# ZYNQ_BANK.net
KiCad netlist of a schematic drawn in Altium Designer
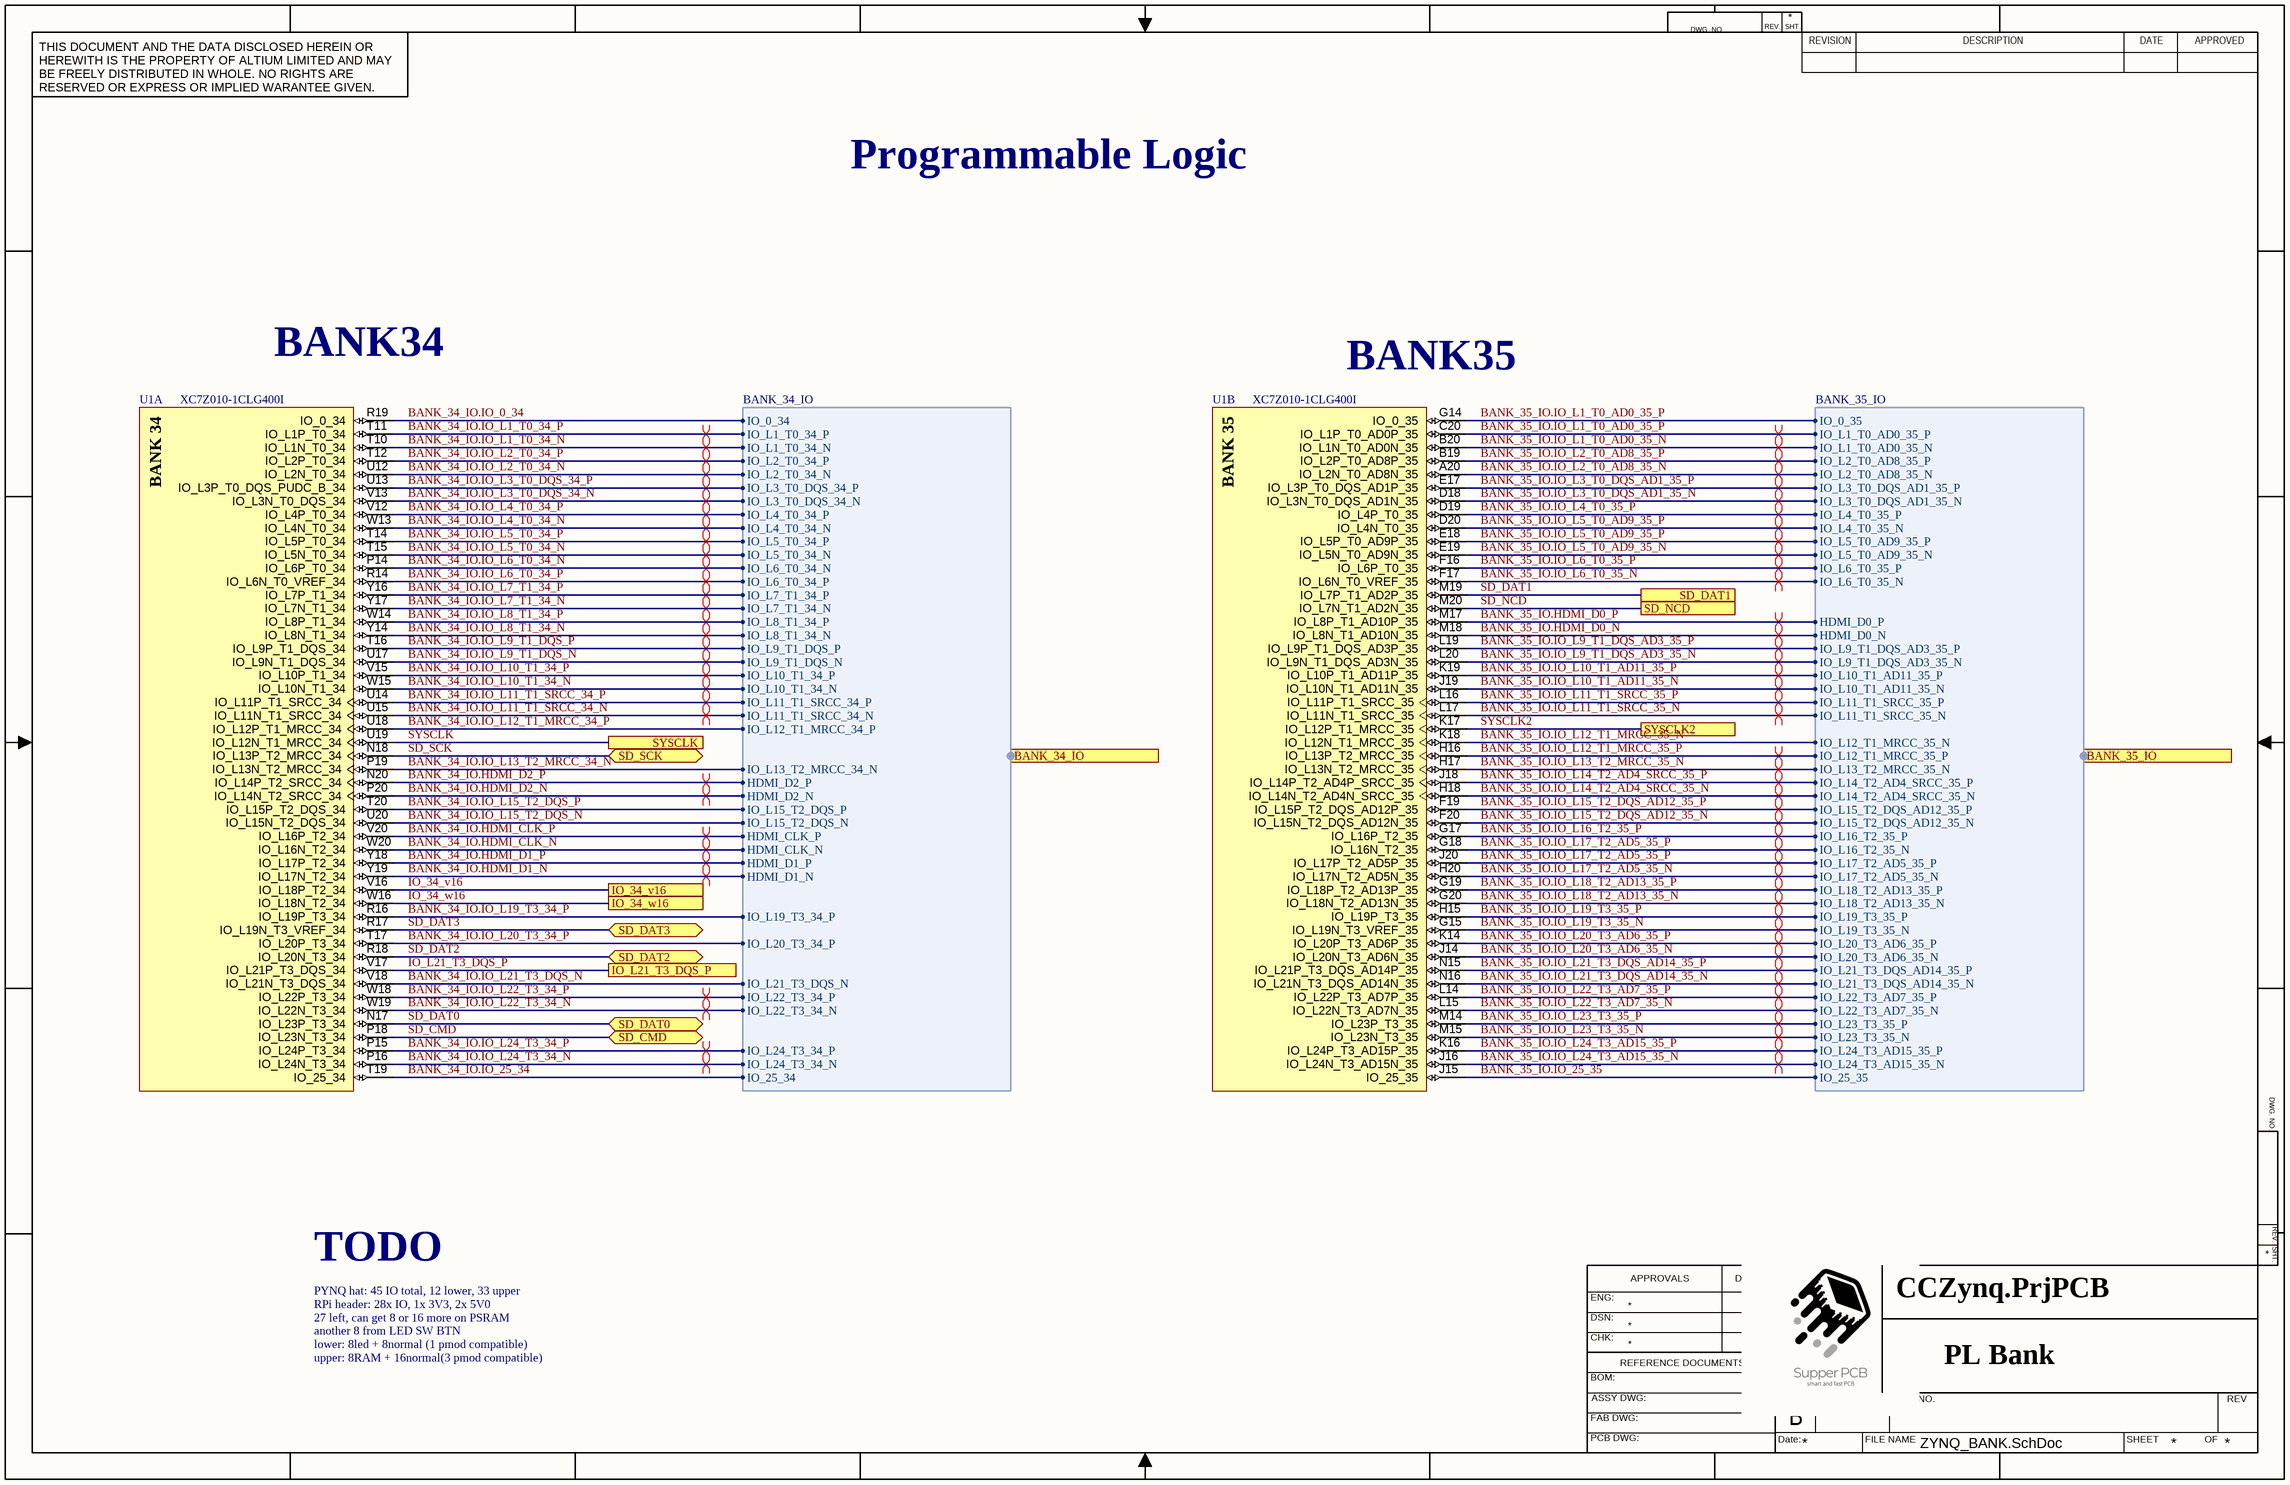
[diagram p0: ZYNQ_BANK.SchDoc]

(export (version "E")
  (design (tool "Eeschema 10.0.6"))
  (components
    (comp (ref "U1")
      (value "XC7Z010-1CLG400I")
      (footprint "CLG400")
      (fields (field (name "GENERIC PART NUMBER") "XC7Z010") (field (name "MANUFACTURER") "Xilinx"))
      (libsource (lib "CCZynq") (part "XC7Z010-1CLG400I"))
    )
  )
  (nets
    (net (code "3") (name "/BANK_34_IO.HDMI_CLK_N") (class "Default")
      (node (ref "U1") (pin "W20") (pinfunction "IO_L16N_T2_34_W20") (pintype "bidirectional"))
    )
    (net (code "4") (name "/BANK_34_IO.HDMI_CLK_P") (class "Default")
      (node (ref "U1") (pin "V20") (pinfunction "IO_L16P_T2_34_V20") (pintype "bidirectional"))
    )
    (net (code "5") (name "/BANK_34_IO.HDMI_D1_N") (class "Default")
      (node (ref "U1") (pin "Y19") (pinfunction "IO_L17N_T2_34_Y19") (pintype "bidirectional"))
    )
    (net (code "6") (name "/BANK_34_IO.HDMI_D1_P") (class "Default")
      (node (ref "U1") (pin "Y18") (pinfunction "IO_L17P_T2_34_Y18") (pintype "bidirectional"))
    )
    (net (code "7") (name "/BANK_34_IO.HDMI_D2_N") (class "Default")
      (node (ref "U1") (pin "P20") (pinfunction "IO_L14N_T2_SRCC_34_P20") (pintype "bidirectional"))
    )
    (net (code "8") (name "/BANK_34_IO.HDMI_D2_P") (class "Default")
      (node (ref "U1") (pin "N20") (pinfunction "IO_L14P_T2_SRCC_34_N20") (pintype "bidirectional"))
    )
    (net (code "9") (name "/BANK_34_IO.IO_0_34") (class "Default")
      (node (ref "U1") (pin "R19") (pinfunction "IO_0_34_R19") (pintype "bidirectional"))
    )
    (net (code "10") (name "/BANK_34_IO.IO_25_34") (class "Default")
      (node (ref "U1") (pin "T19") (pinfunction "IO_25_34_T19") (pintype "bidirectional"))
    )
    (net (code "11") (name "/BANK_34_IO.IO_L1_T0_34_N") (class "Default")
      (node (ref "U1") (pin "T10") (pinfunction "IO_L1N_T0_34_T10") (pintype "bidirectional"))
    )
    (net (code "12") (name "/BANK_34_IO.IO_L1_T0_34_P") (class "Default")
      (node (ref "U1") (pin "T11") (pinfunction "IO_L1P_T0_34_T11") (pintype "bidirectional"))
    )
    (net (code "13") (name "/BANK_34_IO.IO_L2_T0_34_N") (class "Default")
      (node (ref "U1") (pin "U12") (pinfunction "IO_L2N_T0_34_U12") (pintype "bidirectional"))
    )
    (net (code "14") (name "/BANK_34_IO.IO_L2_T0_34_P") (class "Default")
      (node (ref "U1") (pin "T12") (pinfunction "IO_L2P_T0_34_T12") (pintype "bidirectional"))
    )
    (net (code "15") (name "/BANK_34_IO.IO_L3_T0_DQS_34_N") (class "Default")
      (node (ref "U1") (pin "V13") (pinfunction "IO_L3N_T0_DQS_34_V13") (pintype "bidirectional"))
    )
    (net (code "16") (name "/BANK_34_IO.IO_L3_T0_DQS_34_P") (class "Default")
      (node (ref "U1") (pin "U13") (pinfunction "IO_L3P_T0_DQS_PUDC_B_34_U13") (pintype "bidirectional"))
    )
    (net (code "17") (name "/BANK_34_IO.IO_L4_T0_34_N") (class "Default")
      (node (ref "U1") (pin "W13") (pinfunction "IO_L4N_T0_34_W13") (pintype "bidirectional"))
    )
    (net (code "18") (name "/BANK_34_IO.IO_L4_T0_34_P") (class "Default")
      (node (ref "U1") (pin "V12") (pinfunction "IO_L4P_T0_34_V12") (pintype "bidirectional"))
    )
    (net (code "19") (name "/BANK_34_IO.IO_L5_T0_34_N") (class "Default")
      (node (ref "U1") (pin "T15") (pinfunction "IO_L5N_T0_34_T15") (pintype "bidirectional"))
    )
    (net (code "20") (name "/BANK_34_IO.IO_L5_T0_34_P") (class "Default")
      (node (ref "U1") (pin "T14") (pinfunction "IO_L5P_T0_34_T14") (pintype "bidirectional"))
    )
    (net (code "21") (name "/BANK_34_IO.IO_L6_T0_34_N") (class "Default")
      (node (ref "U1") (pin "P14") (pinfunction "IO_L6P_T0_34_P14") (pintype "bidirectional"))
    )
    (net (code "22") (name "/BANK_34_IO.IO_L6_T0_34_P") (class "Default")
      (node (ref "U1") (pin "R14") (pinfunction "IO_L6N_T0_VREF_34_R14") (pintype "bidirectional"))
    )
    (net (code "23") (name "/BANK_34_IO.IO_L7_T1_34_N") (class "Default")
      (node (ref "U1") (pin "Y17") (pinfunction "IO_L7N_T1_34_Y17") (pintype "bidirectional"))
    )
    (net (code "24") (name "/BANK_34_IO.IO_L7_T1_34_P") (class "Default")
      (node (ref "U1") (pin "Y16") (pinfunction "IO_L7P_T1_34_Y16") (pintype "bidirectional"))
    )
    (net (code "25") (name "/BANK_34_IO.IO_L8_T1_34_N") (class "Default")
      (node (ref "U1") (pin "Y14") (pinfunction "IO_L8N_T1_34_Y14") (pintype "bidirectional"))
    )
    (net (code "26") (name "/BANK_34_IO.IO_L8_T1_34_P") (class "Default")
      (node (ref "U1") (pin "W14") (pinfunction "IO_L8P_T1_34_W14") (pintype "bidirectional"))
    )
    (net (code "27") (name "/BANK_34_IO.IO_L9_T1_DQS_N") (class "Default")
      (node (ref "U1") (pin "U17") (pinfunction "IO_L9N_T1_DQS_34_U17") (pintype "bidirectional"))
    )
    (net (code "28") (name "/BANK_34_IO.IO_L9_T1_DQS_P") (class "Default")
      (node (ref "U1") (pin "T16") (pinfunction "IO_L9P_T1_DQS_34_T16") (pintype "bidirectional"))
    )
    (net (code "29") (name "/BANK_34_IO.IO_L10_T1_34_N") (class "Default")
      (node (ref "U1") (pin "W15") (pinfunction "IO_L10N_T1_34_W15") (pintype "bidirectional"))
    )
    (net (code "30") (name "/BANK_34_IO.IO_L10_T1_34_P") (class "Default")
      (node (ref "U1") (pin "V15") (pinfunction "IO_L10P_T1_34_V15") (pintype "bidirectional"))
    )
    (net (code "31") (name "/BANK_34_IO.IO_L11_T1_SRCC_34_N") (class "Default")
      (node (ref "U1") (pin "U15") (pinfunction "IO_L11N_T1_SRCC_34_U15") (pintype "bidirectional"))
    )
    (net (code "32") (name "/BANK_34_IO.IO_L11_T1_SRCC_34_P") (class "Default")
      (node (ref "U1") (pin "U14") (pinfunction "IO_L11P_T1_SRCC_34_U14") (pintype "bidirectional"))
    )
    (net (code "33") (name "/BANK_34_IO.IO_L12_T1_MRCC_34_P") (class "Default")
      (node (ref "U1") (pin "U18") (pinfunction "IO_L12P_T1_MRCC_34_U18") (pintype "bidirectional"))
    )
    (net (code "34") (name "/BANK_34_IO.IO_L13_T2_MRCC_34_N") (class "Default")
      (node (ref "U1") (pin "P19") (pinfunction "IO_L13N_T2_MRCC_34_P19") (pintype "bidirectional"))
    )
    (net (code "35") (name "/BANK_34_IO.IO_L15_T2_DQS_N") (class "Default")
      (node (ref "U1") (pin "U20") (pinfunction "IO_L15N_T2_DQS_34_U20") (pintype "bidirectional"))
    )
    (net (code "36") (name "/BANK_34_IO.IO_L15_T2_DQS_P") (class "Default")
      (node (ref "U1") (pin "T20") (pinfunction "IO_L15P_T2_DQS_34_T20") (pintype "bidirectional"))
    )
    (net (code "37") (name "/BANK_34_IO.IO_L19_T3_34_P") (class "Default")
      (node (ref "U1") (pin "R16") (pinfunction "IO_L19P_T3_34_R16") (pintype "bidirectional"))
    )
    (net (code "38") (name "/BANK_34_IO.IO_L20_T3_34_P") (class "Default")
      (node (ref "U1") (pin "T17") (pinfunction "IO_L20P_T3_34_T17") (pintype "bidirectional"))
    )
    (net (code "39") (name "/BANK_34_IO.IO_L21_T3_DQS_N") (class "Default")
      (node (ref "U1") (pin "V18") (pinfunction "IO_L21N_T3_DQS_34_V18") (pintype "bidirectional"))
    )
    (net (code "40") (name "/BANK_34_IO.IO_L22_T3_34_N") (class "Default")
      (node (ref "U1") (pin "W19") (pinfunction "IO_L22N_T3_34_W19") (pintype "bidirectional"))
    )
    (net (code "41") (name "/BANK_34_IO.IO_L22_T3_34_P") (class "Default")
      (node (ref "U1") (pin "W18") (pinfunction "IO_L22P_T3_34_W18") (pintype "bidirectional"))
    )
    (net (code "42") (name "/BANK_34_IO.IO_L24_T3_34_N") (class "Default")
      (node (ref "U1") (pin "P16") (pinfunction "IO_L24N_T3_34_P16") (pintype "bidirectional"))
    )
    (net (code "43") (name "/BANK_34_IO.IO_L24_T3_34_P") (class "Default")
      (node (ref "U1") (pin "P15") (pinfunction "IO_L24P_T3_34_P15") (pintype "bidirectional"))
    )
    (net (code "44") (name "/BANK_35_IO.HDMI_D0_N") (class "Default")
      (node (ref "U1") (pin "M18") (pinfunction "IO_L8N_T1_AD10N_35_M18") (pintype "bidirectional"))
    )
    (net (code "45") (name "/BANK_35_IO.HDMI_D0_P") (class "Default")
      (node (ref "U1") (pin "M17") (pinfunction "IO_L8P_T1_AD10P_35_M17") (pintype "bidirectional"))
    )
    (net (code "46") (name "/BANK_35_IO.IO_25_35") (class "Default")
      (node (ref "U1") (pin "J15") (pinfunction "IO_25_35_J15") (pintype "bidirectional"))
    )
    (net (code "47") (name "/BANK_35_IO.IO_L1_T0_AD0_35_N") (class "Default")
      (node (ref "U1") (pin "B20") (pinfunction "IO_L1N_T0_AD0N_35_B20") (pintype "bidirectional"))
    )
    (net (code "48") (name "/BANK_35_IO.IO_L1_T0_AD0_35_P") (class "Default")
      (node (ref "U1") (pin "C20") (pinfunction "IO_L1P_T0_AD0P_35_C20") (pintype "bidirectional"))
      (node (ref "U1") (pin "G14") (pinfunction "IO_0_35_G14") (pintype "bidirectional"))
    )
    (net (code "49") (name "/BANK_35_IO.IO_L2_T0_AD8_35_N") (class "Default")
      (node (ref "U1") (pin "A20") (pinfunction "IO_L2N_T0_AD8N_35_A20") (pintype "bidirectional"))
    )
    (net (code "50") (name "/BANK_35_IO.IO_L2_T0_AD8_35_P") (class "Default")
      (node (ref "U1") (pin "B19") (pinfunction "IO_L2P_T0_AD8P_35_B19") (pintype "bidirectional"))
    )
    (net (code "51") (name "/BANK_35_IO.IO_L3_T0_DQS_AD1_35_N") (class "Default")
      (node (ref "U1") (pin "D18") (pinfunction "IO_L3N_T0_DQS_AD1N_35_D18") (pintype "bidirectional"))
    )
    (net (code "52") (name "/BANK_35_IO.IO_L3_T0_DQS_AD1_35_P") (class "Default")
      (node (ref "U1") (pin "E17") (pinfunction "IO_L3P_T0_DQS_AD1P_35_E17") (pintype "bidirectional"))
    )
    (net (code "53") (name "/BANK_35_IO.IO_L4_T0_35_P") (class "Default")
      (node (ref "U1") (pin "D19") (pinfunction "IO_L4P_T0_35_D19") (pintype "bidirectional"))
    )
    (net (code "54") (name "/BANK_35_IO.IO_L5_T0_AD9_35_N") (class "Default")
      (node (ref "U1") (pin "E19") (pinfunction "IO_L5N_T0_AD9N_35_E19") (pintype "bidirectional"))
    )
    (net (code "55") (name "/BANK_35_IO.IO_L5_T0_AD9_35_P") (class "Default")
      (node (ref "U1") (pin "D20") (pinfunction "IO_L4N_T0_35_D20") (pintype "bidirectional"))
      (node (ref "U1") (pin "E18") (pinfunction "IO_L5P_T0_AD9P_35_E18") (pintype "bidirectional"))
    )
    (net (code "56") (name "/BANK_35_IO.IO_L6_T0_35_N") (class "Default")
      (node (ref "U1") (pin "F17") (pinfunction "IO_L6N_T0_VREF_35_F17") (pintype "bidirectional"))
    )
    (net (code "57") (name "/BANK_35_IO.IO_L6_T0_35_P") (class "Default")
      (node (ref "U1") (pin "F16") (pinfunction "IO_L6P_T0_35_F16") (pintype "bidirectional"))
    )
    (net (code "58") (name "/BANK_35_IO.IO_L9_T1_DQS_AD3_35_N") (class "Default")
      (node (ref "U1") (pin "L20") (pinfunction "IO_L9N_T1_DQS_AD3N_35_L20") (pintype "bidirectional"))
    )
    (net (code "59") (name "/BANK_35_IO.IO_L9_T1_DQS_AD3_35_P") (class "Default")
      (node (ref "U1") (pin "L19") (pinfunction "IO_L9P_T1_DQS_AD3P_35_L19") (pintype "bidirectional"))
    )
    (net (code "60") (name "/BANK_35_IO.IO_L10_T1_AD11_35_N") (class "Default")
      (node (ref "U1") (pin "J19") (pinfunction "IO_L10N_T1_AD11N_35_J19") (pintype "bidirectional"))
    )
    (net (code "61") (name "/BANK_35_IO.IO_L10_T1_AD11_35_P") (class "Default")
      (node (ref "U1") (pin "K19") (pinfunction "IO_L10P_T1_AD11P_35_K19") (pintype "bidirectional"))
    )
    (net (code "62") (name "/BANK_35_IO.IO_L11_T1_SRCC_35_N") (class "Default")
      (node (ref "U1") (pin "L17") (pinfunction "IO_L11N_T1_SRCC_35_L17") (pintype "bidirectional"))
    )
    (net (code "63") (name "/BANK_35_IO.IO_L11_T1_SRCC_35_P") (class "Default")
      (node (ref "U1") (pin "L16") (pinfunction "IO_L11P_T1_SRCC_35_L16") (pintype "bidirectional"))
    )
    (net (code "64") (name "/BANK_35_IO.IO_L12_T1_MRCC_35_N") (class "Default")
      (node (ref "U1") (pin "K18") (pinfunction "IO_L12N_T1_MRCC_35_K18") (pintype "bidirectional"))
    )
    (net (code "65") (name "/BANK_35_IO.IO_L12_T1_MRCC_35_P") (class "Default")
      (node (ref "U1") (pin "H16") (pinfunction "IO_L13P_T2_MRCC_35_H16") (pintype "bidirectional"))
    )
    (net (code "66") (name "/BANK_35_IO.IO_L13_T2_MRCC_35_N") (class "Default")
      (node (ref "U1") (pin "H17") (pinfunction "IO_L13N_T2_MRCC_35_H17") (pintype "bidirectional"))
    )
    (net (code "67") (name "/BANK_35_IO.IO_L14_T2_AD4_SRCC_35_N") (class "Default")
      (node (ref "U1") (pin "H18") (pinfunction "IO_L14N_T2_AD4N_SRCC_35_H18") (pintype "bidirectional"))
    )
    (net (code "68") (name "/BANK_35_IO.IO_L14_T2_AD4_SRCC_35_P") (class "Default")
      (node (ref "U1") (pin "J18") (pinfunction "IO_L14P_T2_AD4P_SRCC_35_J18") (pintype "bidirectional"))
    )
    (net (code "69") (name "/BANK_35_IO.IO_L15_T2_DQS_AD12_35_N") (class "Default")
      (node (ref "U1") (pin "F20") (pinfunction "IO_L15N_T2_DQS_AD12N_35_F20") (pintype "bidirectional"))
    )
    (net (code "70") (name "/BANK_35_IO.IO_L15_T2_DQS_AD12_35_P") (class "Default")
      (node (ref "U1") (pin "F19") (pinfunction "IO_L15P_T2_DQS_AD12P_35_F19") (pintype "bidirectional"))
    )
    (net (code "71") (name "/BANK_35_IO.IO_L16_T2_35_P") (class "Default")
      (node (ref "U1") (pin "G17") (pinfunction "IO_L16P_T2_35_G17") (pintype "bidirectional"))
    )
    (net (code "72") (name "/BANK_35_IO.IO_L17_T2_AD5_35_N") (class "Default")
      (node (ref "U1") (pin "H20") (pinfunction "IO_L17N_T2_AD5N_35_H20") (pintype "bidirectional"))
    )
    (net (code "73") (name "/BANK_35_IO.IO_L17_T2_AD5_35_P") (class "Default")
      (node (ref "U1") (pin "G18") (pinfunction "IO_L16N_T2_35_G18") (pintype "bidirectional"))
      (node (ref "U1") (pin "J20") (pinfunction "IO_L17P_T2_AD5P_35_J20") (pintype "bidirectional"))
    )
    (net (code "74") (name "/BANK_35_IO.IO_L18_T2_AD13_35_N") (class "Default")
      (node (ref "U1") (pin "G20") (pinfunction "IO_L18N_T2_AD13N_35_G20") (pintype "bidirectional"))
    )
    (net (code "75") (name "/BANK_35_IO.IO_L18_T2_AD13_35_P") (class "Default")
      (node (ref "U1") (pin "G19") (pinfunction "IO_L18P_T2_AD13P_35_G19") (pintype "bidirectional"))
    )
    (net (code "76") (name "/BANK_35_IO.IO_L19_T3_35_N") (class "Default")
      (node (ref "U1") (pin "G15") (pinfunction "IO_L19N_T3_VREF_35_G15") (pintype "bidirectional"))
    )
    (net (code "77") (name "/BANK_35_IO.IO_L19_T3_35_P") (class "Default")
      (node (ref "U1") (pin "H15") (pinfunction "IO_L19P_T3_35_H15") (pintype "bidirectional"))
    )
    (net (code "78") (name "/BANK_35_IO.IO_L20_T3_AD6_35_N") (class "Default")
      (node (ref "U1") (pin "J14") (pinfunction "IO_L20N_T3_AD6N_35_J14") (pintype "bidirectional"))
    )
    (net (code "79") (name "/BANK_35_IO.IO_L20_T3_AD6_35_P") (class "Default")
      (node (ref "U1") (pin "K14") (pinfunction "IO_L20P_T3_AD6P_35_K14") (pintype "bidirectional"))
    )
    (net (code "80") (name "/BANK_35_IO.IO_L21_T3_DQS_AD14_35_N") (class "Default")
      (node (ref "U1") (pin "N16") (pinfunction "IO_L21N_T3_DQS_AD14N_35_N16") (pintype "bidirectional"))
    )
    (net (code "81") (name "/BANK_35_IO.IO_L21_T3_DQS_AD14_35_P") (class "Default")
      (node (ref "U1") (pin "N15") (pinfunction "IO_L21P_T3_DQS_AD14P_35_N15") (pintype "bidirectional"))
    )
    (net (code "82") (name "/BANK_35_IO.IO_L22_T3_AD7_35_N") (class "Default")
      (node (ref "U1") (pin "L15") (pinfunction "IO_L22N_T3_AD7N_35_L15") (pintype "bidirectional"))
    )
    (net (code "83") (name "/BANK_35_IO.IO_L22_T3_AD7_35_P") (class "Default")
      (node (ref "U1") (pin "L14") (pinfunction "IO_L22P_T3_AD7P_35_L14") (pintype "bidirectional"))
    )
    (net (code "84") (name "/BANK_35_IO.IO_L23_T3_35_N") (class "Default")
      (node (ref "U1") (pin "M15") (pinfunction "IO_L23N_T3_35_M15") (pintype "bidirectional"))
    )
    (net (code "85") (name "/BANK_35_IO.IO_L23_T3_35_P") (class "Default")
      (node (ref "U1") (pin "M14") (pinfunction "IO_L23P_T3_35_M14") (pintype "bidirectional"))
    )
    (net (code "86") (name "/BANK_35_IO.IO_L24_T3_AD15_35_N") (class "Default")
      (node (ref "U1") (pin "J16") (pinfunction "IO_L24N_T3_AD15N_35_J16") (pintype "bidirectional"))
    )
    (net (code "87") (name "/BANK_35_IO.IO_L24_T3_AD15_35_P") (class "Default")
      (node (ref "U1") (pin "K16") (pinfunction "IO_L24P_T3_AD15P_35_K16") (pintype "bidirectional"))
    )
    (net (code "88") (name "/IO_34_v16") (class "Default")
      (node (ref "U1") (pin "V16") (pinfunction "IO_L18P_T2_34_V16") (pintype "bidirectional"))
    )
    (net (code "89") (name "/IO_34_w16") (class "Default")
      (node (ref "U1") (pin "W16") (pinfunction "IO_L18N_T2_34_W16") (pintype "bidirectional"))
    )
    (net (code "90") (name "/IO_L21_T3_DQS_P") (class "Default")
      (node (ref "U1") (pin "V17") (pinfunction "IO_L21P_T3_DQS_34_V17") (pintype "bidirectional"))
    )
    (net (code "91") (name "/SD_CMD") (class "Default")
      (node (ref "U1") (pin "P18") (pinfunction "IO_L23N_T3_34_P18") (pintype "bidirectional"))
    )
    (net (code "92") (name "/SD_DAT0") (class "Default")
      (node (ref "U1") (pin "N17") (pinfunction "IO_L23P_T3_34_N17") (pintype "bidirectional"))
    )
    (net (code "93") (name "/SD_DAT1") (class "Default")
      (node (ref "U1") (pin "M19") (pinfunction "IO_L7P_T1_AD2P_35_M19") (pintype "bidirectional"))
    )
    (net (code "94") (name "/SD_DAT2") (class "Default")
      (node (ref "U1") (pin "R18") (pinfunction "IO_L20N_T3_34_R18") (pintype "bidirectional"))
    )
    (net (code "95") (name "/SD_DAT3") (class "Default")
      (node (ref "U1") (pin "R17") (pinfunction "IO_L19N_T3_VREF_34_R17") (pintype "bidirectional"))
    )
    (net (code "96") (name "/SD_NCD") (class "Default")
      (node (ref "U1") (pin "M20") (pinfunction "IO_L7N_T1_AD2N_35_M20") (pintype "bidirectional"))
    )
    (net (code "97") (name "/SD_SCK") (class "Default")
      (node (ref "U1") (pin "N18") (pinfunction "IO_L13P_T2_MRCC_34_N18") (pintype "bidirectional"))
    )
    (net (code "98") (name "/SYSCLK") (class "Default")
      (node (ref "U1") (pin "U19") (pinfunction "IO_L12N_T1_MRCC_34_U19") (pintype "bidirectional"))
    )
    (net (code "99") (name "/SYSCLK2") (class "Default")
      (node (ref "U1") (pin "K17") (pinfunction "IO_L12P_T1_MRCC_35_K17") (pintype "bidirectional"))
    )
  )
)
